# PicoUSBMotherboardV1_1.net
KiCad netlist of a schematic drawn in EasyEDA Pro
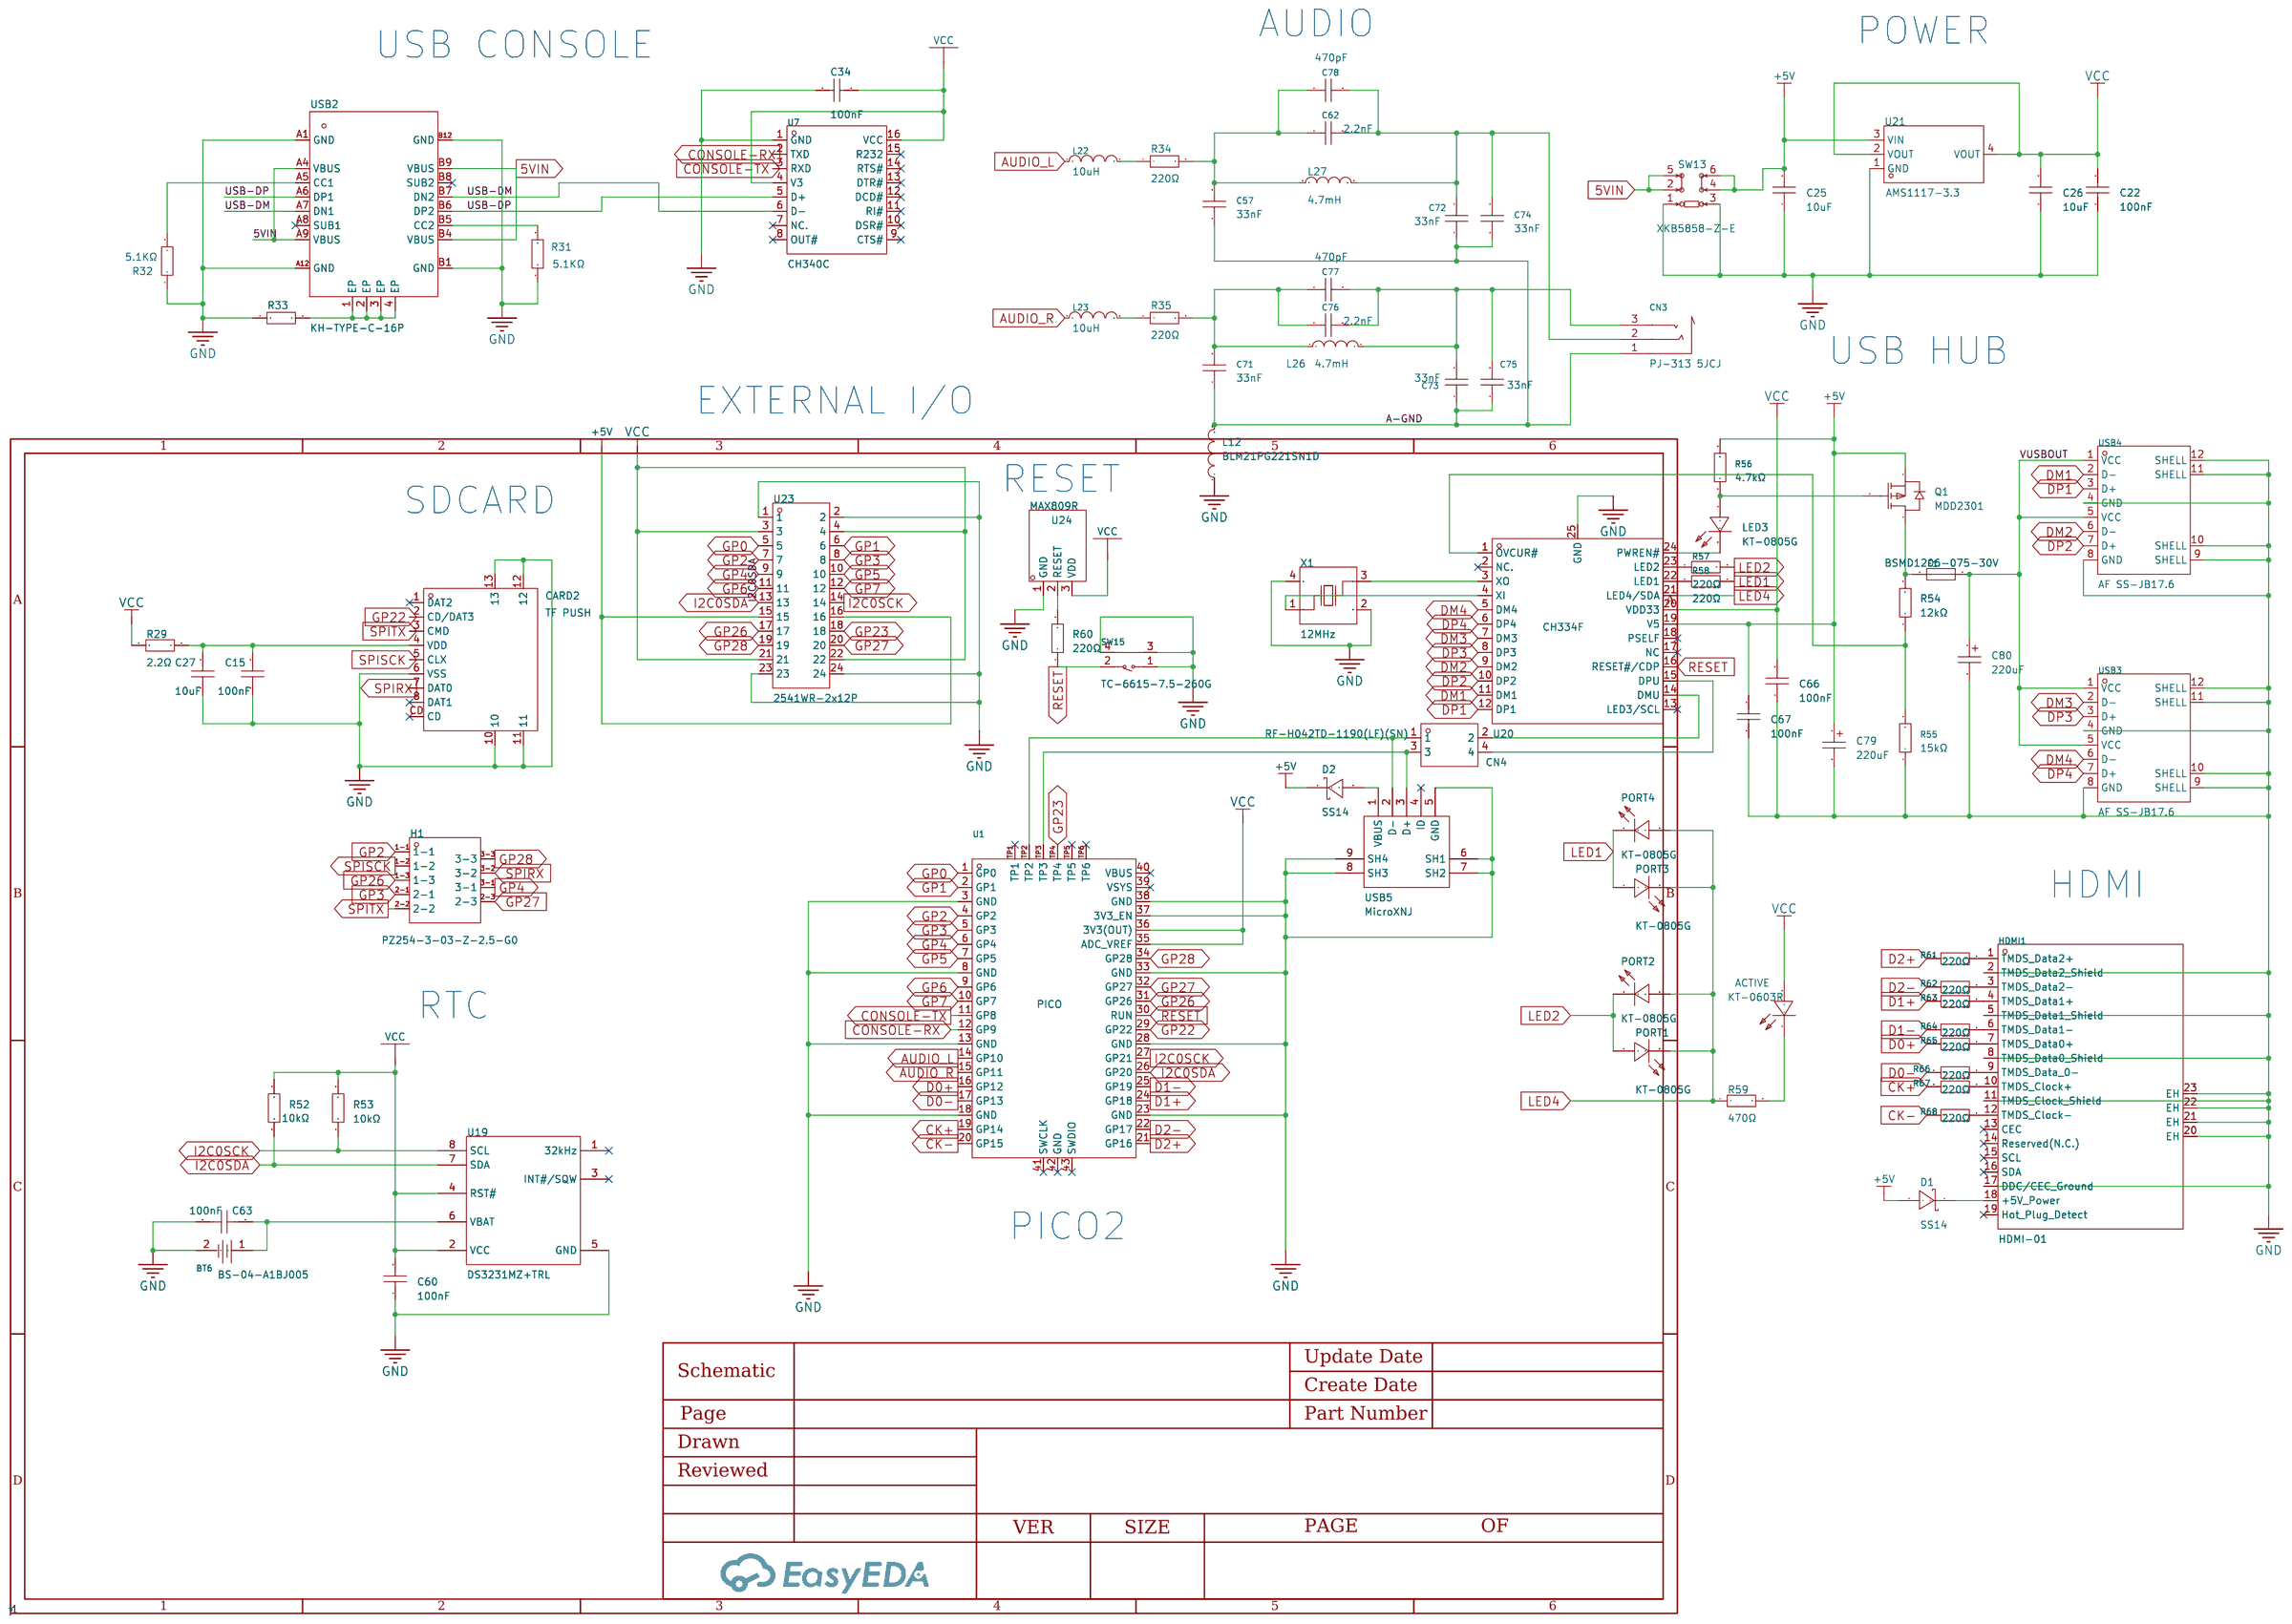
[diagram p0: schematic sheet]

(export (version "E")
  (design (tool "Eeschema 10.0.6"))
  (components
    (comp (ref "ACTIVE")
      (value "KT-0603R")
      (footprint "easyedapro:LED0603-RD")
      (fields (field (name "Manufacturer") "KENTO"))
      (libsource (lib "easyedapro") (part "KT-0603R"))
    )
    (comp (ref "BT6")
      (value "BS-04-A1BJ005")
      (footprint "easyedapro:BAT-TH_BS-04-A1BJ004")
      (fields (field (name "Manufacturer") "MYOUNG(美阳)"))
      (libsource (lib "easyedapro") (part "BS-04-A1BJ005"))
    )
    (comp (ref "C15")
      (value "100nF")
      (fields
        (field (name "Manufacturer Part") "CL05B104KO5NNNC")
        (field (name "Manufacturer") "SAMSUNG(三星)")
      )
      (libsource (lib "easyedapro") (part "cl10a225ko8nnnc"))
    )
    (comp (ref "C22")
      (value "100nF")
      (fields
        (field (name "Manufacturer Part") "CL05B104KO5NNNC")
        (field (name "Manufacturer") "SAMSUNG(三星)")
      )
      (libsource (lib "easyedapro") (part "cl10a225ko8nnnc"))
    )
    (comp (ref "C25")
      (value "10uF")
      (footprint "easyedapro:C1206")
      (fields
        (field (name "Manufacturer Part") "CL31A106KBHNNNE")
        (field (name "Manufacturer") "SAMSUNG(三星)")
      )
      (libsource (lib "easyedapro") (part "CL31A106KBHNNNE"))
    )
    (comp (ref "C26")
      (value "10uF")
      (footprint "easyedapro:C1206")
      (fields
        (field (name "Manufacturer Part") "CL31A106KBHNNNE")
        (field (name "Manufacturer") "SAMSUNG(三星)")
      )
      (libsource (lib "easyedapro") (part "CL31A106KBHNNNE"))
    )
    (comp (ref "C27")
      (value "10uF")
      (footprint "easyedapro:C1206")
      (fields
        (field (name "Manufacturer Part") "CL31A106KBHNNNE")
        (field (name "Manufacturer") "SAMSUNG(三星)")
      )
      (libsource (lib "easyedapro") (part "CL31A106KBHNNNE"))
    )
    (comp (ref "C34")
      (value "100nF")
      (fields
        (field (name "Manufacturer Part") "CL05B104KO5NNNC")
        (field (name "Manufacturer") "SAMSUNG(三星)")
      )
      (libsource (lib "easyedapro") (part "cl10a225ko8nnnc"))
    )
    (comp (ref "C57")
      (value "33nF")
      (footprint "easyedapro:C0805")
      (fields (field (name "Manufacturer Part") "0805B333K500NT") (field (name "Manufacturer") "FH(风华)"))
      (libsource (lib "easyedapro") (part "0805B333K500NT"))
    )
    (comp (ref "C60")
      (value "100nF")
      (fields
        (field (name "Manufacturer Part") "CL05B104KO5NNNC")
        (field (name "Manufacturer") "SAMSUNG(三星)")
      )
      (libsource (lib "easyedapro") (part "CL10A225KO8NNNC"))
    )
    (comp (ref "C62")
      (value "2.2nF")
      (footprint "easyedapro:C0805")
      (fields
        (field (name "Manufacturer Part") "CL21C222JBFNNNE")
        (field (name "Manufacturer") "SAMSUNG(三星)")
      )
      (libsource (lib "easyedapro") (part "CL21C222JBFNNNE"))
    )
    (comp (ref "C63")
      (value "100nF")
      (footprint "easyedapro:C0402")
      (fields
        (field (name "Manufacturer Part") "CL05B104KB54PNC")
        (field (name "Manufacturer") "SAMSUNG(三星)")
      )
      (libsource (lib "easyedapro") (part "CL05B104KB54PNC"))
    )
    (comp (ref "C66")
      (value "100nF")
      (fields
        (field (name "Manufacturer Part") "CL05B104KO5NNNC")
        (field (name "Manufacturer") "SAMSUNG(三星)")
      )
      (libsource (lib "easyedapro") (part "cl10a225ko8nnnc"))
    )
    (comp (ref "C67")
      (value "100nF")
      (fields
        (field (name "Manufacturer Part") "CL05B104KO5NNNC")
        (field (name "Manufacturer") "SAMSUNG(三星)")
      )
      (libsource (lib "easyedapro") (part "cl10a225ko8nnnc"))
    )
    (comp (ref "C71")
      (value "33nF")
      (footprint "easyedapro:C0805")
      (fields (field (name "Manufacturer Part") "0805B333K500NT") (field (name "Manufacturer") "FH(风华)"))
      (libsource (lib "easyedapro") (part "0805B333K500NT"))
    )
    (comp (ref "C72")
      (value "33nF")
      (footprint "easyedapro:C0805")
      (fields (field (name "Manufacturer Part") "0805B333K500NT") (field (name "Manufacturer") "FH(风华)"))
      (libsource (lib "easyedapro") (part "0805B333K500NT"))
    )
    (comp (ref "C73")
      (value "33nF")
      (footprint "easyedapro:C0805")
      (fields (field (name "Manufacturer Part") "0805B333K500NT") (field (name "Manufacturer") "FH(风华)"))
      (libsource (lib "easyedapro") (part "0805B333K500NT"))
    )
    (comp (ref "C74")
      (value "33nF")
      (footprint "easyedapro:C0805")
      (fields (field (name "Manufacturer Part") "0805B333K500NT") (field (name "Manufacturer") "FH(风华)"))
      (libsource (lib "easyedapro") (part "0805B333K500NT"))
    )
    (comp (ref "C75")
      (value "33nF")
      (footprint "easyedapro:C0805")
      (fields (field (name "Manufacturer Part") "0805B333K500NT") (field (name "Manufacturer") "FH(风华)"))
      (libsource (lib "easyedapro") (part "0805B333K500NT"))
    )
    (comp (ref "C76")
      (value "2.2nF")
      (footprint "easyedapro:C0805")
      (fields
        (field (name "Manufacturer Part") "CL21C222JBFNNNE")
        (field (name "Manufacturer") "SAMSUNG(三星)")
      )
      (libsource (lib "easyedapro") (part "CL21C222JBFNNNE"))
    )
    (comp (ref "C77")
      (value "470pF")
      (footprint "easyedapro:C0603")
      (fields (field (name "Manufacturer Part") "0603B471K500NT") (field (name "Manufacturer") "FH(风华)"))
      (libsource (lib "easyedapro") (part "0603B471K500NT"))
    )
    (comp (ref "C78")
      (value "470pF")
      (footprint "easyedapro:C0603")
      (fields (field (name "Manufacturer Part") "0603B471K500NT") (field (name "Manufacturer") "FH(风华)"))
      (libsource (lib "easyedapro") (part "0603B471K500NT"))
    )
    (comp (ref "C79")
      (value "220uF")
      (footprint "easyedapro:CASE-D_7343")
      (fields (field (name "Manufacturer Part") "TAJD227K010RNJ") (field (name "Manufacturer") "Kyocera AVX"))
      (libsource (lib "easyedapro") (part "TAJD227K010RNJ"))
    )
    (comp (ref "C80")
      (value "220uF")
      (footprint "easyedapro:CASE-D_7343")
      (fields (field (name "Manufacturer Part") "TAJD227K010RNJ") (field (name "Manufacturer") "Kyocera AVX"))
      (libsource (lib "easyedapro") (part "TAJD227K010RNJ"))
    )
    (comp (ref "CARD2")
      (value "TF PUSH")
      (footprint "easyedapro:TF-SMD_TF-PUSH")
      (fields (field (name "Manufacturer") "SHOU HAN(首韩)"))
      (libsource (lib "easyedapro") (part "TF PUSH"))
    )
    (comp (ref "CN3")
      (value "PJ-313 5JCJ")
      (footprint "easyedapro:AUDIO-TH_PJ-313_5JCJ")
      (fields (field (name "Manufacturer") "SHOU HAN(首韩)"))
      (libsource (lib "easyedapro") (part "PJ-313 5JCJ"))
    )
    (comp (ref "CN4")
      (value "RF-H042TD-1190(LF)(SN)")
      (footprint "easyedapro:HDR-TH_4P-P2.54-V-M-R2-C2-S2.54-1")
      (fields (field (name "Manufacturer") "JST"))
      (libsource (lib "easyedapro") (part "RF-H042TD-1190 (LF)(SN)"))
    )
    (comp (ref "D1")
      (value "SS14")
      (footprint "easyedapro:SMA_L4.2-W2.6-LS5.3-RD")
      (fields (field (name "Manufacturer") "MDD(辰达半导体)"))
      (libsource (lib "easyedapro") (part "SS14"))
    )
    (comp (ref "D2")
      (value "SS14")
      (footprint "easyedapro:SMA_L4.2-W2.6-LS5.3-RD")
      (fields (field (name "Manufacturer") "MDD(辰达半导体)"))
      (libsource (lib "easyedapro") (part "SS14"))
    )
    (comp (ref "F1")
      (value "BSMD1206-075-30V")
      (footprint "easyedapro:F1206")
      (fields (field (name "Manufacturer") "BHFUSE(佰宏)"))
      (libsource (lib "easyedapro") (part "BSMD1206-075-30V"))
    )
    (comp (ref "H1")
      (value "PZ254-3-03-Z-2.5-G0")
      (footprint "easyedapro:HDR-TH_9P-P2.54-V-M-R3-C3-S2.54")
      (fields (field (name "Manufacturer") "HCTL(华灿天禄)"))
      (libsource (lib "easyedapro") (part "PZ254-3-03-Z-2.5-G0"))
    )
    (comp (ref "HDMI1")
      (value "HDMI-01")
      (footprint "easyedapro:USB-SMD_HDMI-01")
      (fields (field (name "Manufacturer") "HCTL(华灿天禄)"))
      (libsource (lib "easyedapro") (part "HDMI-01"))
    )
    (comp (ref "L12")
      (value "BLM21PG221SN1D")
      (footprint "easyedapro:L0805")
      (fields (field (name "Manufacturer") "muRata(村田)"))
      (libsource (lib "easyedapro") (part "BLM21PG221SN1D"))
    )
    (comp (ref "L22")
      (value "10uH")
      (footprint "easyedapro:L0805")
      (fields
        (field (name "Manufacturer Part") "SDFL2012S100KTF")
        (field (name "Manufacturer") "Sunlord(顺络)")
      )
      (libsource (lib "easyedapro") (part "SDFL2012S100KTF"))
    )
    (comp (ref "L23")
      (value "10uH")
      (footprint "easyedapro:L0805")
      (fields
        (field (name "Manufacturer Part") "SDFL2012S100KTF")
        (field (name "Manufacturer") "Sunlord(顺络)")
      )
      (libsource (lib "easyedapro") (part "SDFL2012S100KTF"))
    )
    (comp (ref "L26")
      (value "4.7mH")
      (footprint "easyedapro:IND-SMD_L5.0-W5.0-1")
      (fields (field (name "Manufacturer Part") "YNR5040-472M") (field (name "Manufacturer") "YJYCOIN(益嘉源)"))
      (libsource (lib "easyedapro") (part "YNR5040-472M"))
    )
    (comp (ref "L27")
      (value "4.7mH")
      (footprint "easyedapro:IND-SMD_L5.0-W5.0-1")
      (fields (field (name "Manufacturer Part") "YNR5040-472M") (field (name "Manufacturer") "YJYCOIN(益嘉源)"))
      (libsource (lib "easyedapro") (part "YNR5040-472M"))
    )
    (comp (ref "LED3")
      (value "KT-0805G")
      (footprint "easyedapro:LED0805-R-RD")
      (fields (field (name "Manufacturer") "KENTO"))
      (libsource (lib "easyedapro") (part "0805G (Green)"))
    )
    (comp (ref "PORT1")
      (value "KT-0805G")
      (footprint "easyedapro:LED0805-R-RD")
      (fields (field (name "Manufacturer") "KENTO"))
      (libsource (lib "easyedapro") (part "0805G (Green)"))
    )
    (comp (ref "PORT2")
      (value "KT-0805G")
      (footprint "easyedapro:LED0805-R-RD")
      (fields (field (name "Manufacturer") "KENTO"))
      (libsource (lib "easyedapro") (part "0805G (Green)"))
    )
    (comp (ref "PORT3")
      (value "KT-0805G")
      (footprint "easyedapro:LED0805-R-RD")
      (fields (field (name "Manufacturer") "KENTO"))
      (libsource (lib "easyedapro") (part "0805G (Green)"))
    )
    (comp (ref "PORT4")
      (value "KT-0805G")
      (footprint "easyedapro:LED0805-R-RD")
      (fields (field (name "Manufacturer") "KENTO"))
      (libsource (lib "easyedapro") (part "0805G (Green)"))
    )
    (comp (ref "Q1")
      (value "MDD2301")
      (footprint "easyedapro:SOT-23-3_L2.9-W1.5-P1.90-LS2.6-BL")
      (fields (field (name "Manufacturer") "MDD(辰达半导体)"))
      (libsource (lib "easyedapro") (part "SI2301_C427391"))
    )
    (comp (ref "R29")
      (value "2.2Ω")
      (footprint "easyedapro:R0805")
      (fields (field (name "Manufacturer") "UNI-ROYAL(厚声)"))
      (libsource (lib "easyedapro") (part "0805W8F220KT5E"))
    )
    (comp (ref "R31")
      (value "5.1kΩ")
      (fields
        (field (name "Manufacturer Part") "5.1KΩ")
        (field (name "Manufacturer") "UNI-ROYAL(厚声)")
        (field (name "Tolerance") "±1%")
      )
      (libsource (lib "easyedapro") (part "0603waf5101t5e"))
    )
    (comp (ref "R32")
      (value "5.1kΩ")
      (fields
        (field (name "Manufacturer Part") "5.1KΩ")
        (field (name "Manufacturer") "UNI-ROYAL(厚声)")
        (field (name "Tolerance") "±1%")
      )
      (libsource (lib "easyedapro") (part "0603waf5101t5e"))
    )
    (comp (ref "R33")
      (value "1MΩ")
      (fields
        (field (name "Manufacturer Part") "0402WGF1004TCE")
        (field (name "Manufacturer") "UNI-ROYAL(厚声)")
      )
      (libsource (lib "easyedapro") (part "0603waf1004t5e"))
    )
    (comp (ref "R34")
      (value "220Ω")
      (footprint "easyedapro:R0603")
      (fields
        (field (name "Manufacturer Part") "0603WAF2200T5E")
        (field (name "Manufacturer") "UNI-ROYAL(厚声)")
      )
      (libsource (lib "easyedapro") (part "0603WAF2200T5E"))
    )
    (comp (ref "R35")
      (value "220Ω")
      (footprint "easyedapro:R0603")
      (fields
        (field (name "Manufacturer Part") "0603WAF2200T5E")
        (field (name "Manufacturer") "UNI-ROYAL(厚声)")
      )
      (libsource (lib "easyedapro") (part "0603WAF2200T5E"))
    )
    (comp (ref "R52")
      (value "10kΩ")
      (footprint "easyedapro:R0805")
      (fields
        (field (name "Manufacturer Part") "0805W8F1002T5E")
        (field (name "Manufacturer") "UNI-ROYAL(厚声)")
      )
      (libsource (lib "easyedapro") (part "0805W8F1002T5E"))
    )
    (comp (ref "R53")
      (value "10kΩ")
      (footprint "easyedapro:R0805")
      (fields
        (field (name "Manufacturer Part") "0805W8F1002T5E")
        (field (name "Manufacturer") "UNI-ROYAL(厚声)")
      )
      (libsource (lib "easyedapro") (part "0805W8F1002T5E"))
    )
    (comp (ref "R54")
      (value "12kΩ")
      (footprint "easyedapro:R0603")
      (fields
        (field (name "Manufacturer Part") "0603WAF1202T5E")
        (field (name "Manufacturer") "UNI-ROYAL(厚声)")
      )
      (libsource (lib "easyedapro") (part "0603WAF1202T5E"))
    )
    (comp (ref "R55")
      (value "15kΩ")
      (footprint "easyedapro:R0603")
      (fields
        (field (name "Manufacturer Part") "0603WAF1502T5E")
        (field (name "Manufacturer") "UNI-ROYAL(厚声)")
      )
      (libsource (lib "easyedapro") (part "0603WAF1502T5E"))
    )
    (comp (ref "R56")
      (value "4.7kΩ")
      (footprint "easyedapro:R0805")
      (fields
        (field (name "Manufacturer Part") "0805W8F4701T5E")
        (field (name "Manufacturer") "UNI-ROYAL(厚声)")
      )
      (libsource (lib "easyedapro") (part "0805W8F4701T5E"))
    )
    (comp (ref "R57")
      (value "220Ω")
      (footprint "easyedapro:R0805")
      (fields
        (field (name "Manufacturer Part") "0805W8F2200T5E")
        (field (name "Manufacturer") "UNI-ROYAL(厚声)")
      )
      (libsource (lib "easyedapro") (part "0805W8F2200T5E"))
    )
    (comp (ref "R58")
      (value "220Ω")
      (footprint "easyedapro:R0805")
      (fields
        (field (name "Manufacturer Part") "0805W8F2200T5E")
        (field (name "Manufacturer") "UNI-ROYAL(厚声)")
      )
      (libsource (lib "easyedapro") (part "0805W8F2200T5E"))
    )
    (comp (ref "R59")
      (value "470Ω")
      (footprint "easyedapro:R0603")
      (fields
        (field (name "Manufacturer Part") "0603WAF4700T5E")
        (field (name "Manufacturer") "UNI-ROYAL(厚声)")
      )
      (libsource (lib "easyedapro") (part "0603WAF4700T5E"))
    )
    (comp (ref "R60")
      (value "220Ω")
      (footprint "easyedapro:R0603")
      (fields
        (field (name "Manufacturer Part") "0603WAF2200T5E")
        (field (name "Manufacturer") "UNI-ROYAL(厚声)")
      )
      (libsource (lib "easyedapro") (part "0603WAF2200T5E"))
    )
    (comp (ref "R61")
      (value "220Ω")
      (footprint "easyedapro:R0603")
      (fields
        (field (name "Manufacturer Part") "0603WAF2200T5E")
        (field (name "Manufacturer") "UNI-ROYAL(厚声)")
      )
      (libsource (lib "easyedapro") (part "0603WAF2200T5E"))
    )
    (comp (ref "R62")
      (value "220Ω")
      (footprint "easyedapro:R0603")
      (fields
        (field (name "Manufacturer Part") "0603WAF2200T5E")
        (field (name "Manufacturer") "UNI-ROYAL(厚声)")
      )
      (libsource (lib "easyedapro") (part "0603WAF2200T5E"))
    )
    (comp (ref "R63")
      (value "220Ω")
      (footprint "easyedapro:R0603")
      (fields
        (field (name "Manufacturer Part") "0603WAF2200T5E")
        (field (name "Manufacturer") "UNI-ROYAL(厚声)")
      )
      (libsource (lib "easyedapro") (part "0603WAF2200T5E"))
    )
    (comp (ref "R64")
      (value "220Ω")
      (footprint "easyedapro:R0603")
      (fields
        (field (name "Manufacturer Part") "0603WAF2200T5E")
        (field (name "Manufacturer") "UNI-ROYAL(厚声)")
      )
      (libsource (lib "easyedapro") (part "0603WAF2200T5E"))
    )
    (comp (ref "R65")
      (value "220Ω")
      (footprint "easyedapro:R0603")
      (fields
        (field (name "Manufacturer Part") "0603WAF2200T5E")
        (field (name "Manufacturer") "UNI-ROYAL(厚声)")
      )
      (libsource (lib "easyedapro") (part "0603WAF2200T5E"))
    )
    (comp (ref "R66")
      (value "220Ω")
      (footprint "easyedapro:R0603")
      (fields
        (field (name "Manufacturer Part") "0603WAF2200T5E")
        (field (name "Manufacturer") "UNI-ROYAL(厚声)")
      )
      (libsource (lib "easyedapro") (part "0603WAF2200T5E"))
    )
    (comp (ref "R67")
      (value "220Ω")
      (footprint "easyedapro:R0603")
      (fields
        (field (name "Manufacturer Part") "0603WAF2200T5E")
        (field (name "Manufacturer") "UNI-ROYAL(厚声)")
      )
      (libsource (lib "easyedapro") (part "0603WAF2200T5E"))
    )
    (comp (ref "R68")
      (value "220Ω")
      (footprint "easyedapro:R0603")
      (fields
        (field (name "Manufacturer Part") "0603WAF2200T5E")
        (field (name "Manufacturer") "UNI-ROYAL(厚声)")
      )
      (libsource (lib "easyedapro") (part "0603WAF2200T5E"))
    )
    (comp (ref "SW13")
      (value "XKB5858-Z-E")
      (footprint "easyedapro:SW-TH_XKB5858-Z-E")
      (fields (field (name "Manufacturer") "XKB Connectivity(中国星坤)"))
      (libsource (lib "easyedapro") (part "XKB5858-Z-E"))
    )
    (comp (ref "SW15")
      (value "TC-6615-7.5-260G")
      (footprint "easyedapro:SW-TH_4P-L7.5-W7.5-P4.50")
      (fields (field (name "Manufacturer") "HCTL(华灿天禄)"))
      (libsource (lib "easyedapro") (part "TC-6615-7.5-260G"))
    )
    (comp (ref "U1")
      (value "PICO")
      (footprint "easyedapro:COMM-SMD_L51.0-W21.0-P2.54_SC0916")
      (fields (field (name "Manufacturer") "Raspberry Pi(树莓派)"))
      (libsource (lib "easyedapro") (part "PICO"))
    )
    (comp (ref "U7")
      (value "CH340C")
      (footprint "easyedapro:SOP-16_L10.0-W3.9-P1.27-LS6.0-BL")
      (fields (field (name "Manufacturer") "WCH(南京沁恒)"))
      (libsource (lib "easyedapro") (part "CH340C"))
    )
    (comp (ref "U19")
      (value "DS3231MZ+TRL")
      (footprint "easyedapro:SOIC-8_L4.9-W3.9-P1.27-LS6.0-BL")
      (fields (field (name "Manufacturer") "ADI(亚德诺)/MAXIM(美信)"))
      (libsource (lib "easyedapro") (part "DS3231MZ+"))
    )
    (comp (ref "U20")
      (value "CH334F")
      (footprint "easyedapro:QFN-24_L4.0-W4.0-P0.50-BL-EP2.8")
      (fields (field (name "Manufacturer") "WCH(南京沁恒)"))
      (libsource (lib "easyedapro") (part "CH334F_C5187527"))
    )
    (comp (ref "U21")
      (value "AMS1117-3.3")
      (footprint "easyedapro:SOT-223-3_L6.5-W3.4-P2.30-LS7.0-BR")
      (fields (field (name "Manufacturer") "AMS"))
      (libsource (lib "easyedapro") (part "AMS1117-3.3"))
    )
    (comp (ref "U23")
      (value "2541WR-2x12P")
      (footprint "easyedapro:HDR-TH_24P-P2.54-H-M-R2-C12-S2.54-N")
      (fields (field (name "Manufacturer") "HanElectricity(瀚源)"))
      (libsource (lib "easyedapro") (part "2541WR-2X12P"))
    )
    (comp (ref "U24")
      (value "MAX809R")
      (footprint "easyedapro:SOT-23-3_L2.9-W1.3-P1.90-LS2.4-BR")
      (fields (field (name "Manufacturer") "UMW(友台半导体)"))
      (libsource (lib "easyedapro") (part "MAX809R"))
    )
    (comp (ref "USB2")
      (value "KH-TYPE-C-16P")
      (footprint "easyedapro:USB-C-SMD_KH-TYPE-C-16P")
      (fields (field (name "Manufacturer") "kinghelm(金航标)"))
      (libsource (lib "easyedapro") (part "KH-TYPE-C-16P"))
    )
    (comp (ref "USB3")
      (value "AF SS-JB17.6")
      (footprint "easyedapro:USB-A-TH_AF-SS-JB17.6")
      (fields (field (name "Manufacturer") "SHOU HAN(首韩)"))
      (libsource (lib "easyedapro") (part "AF SS-JB17.6"))
    )
    (comp (ref "USB4")
      (value "AF SS-JB17.6")
      (footprint "easyedapro:USB-A-TH_AF-SS-JB17.6")
      (fields (field (name "Manufacturer") "SHOU HAN(首韩)"))
      (libsource (lib "easyedapro") (part "AF SS-JB17.6"))
    )
    (comp (ref "USB5")
      (value "MicroXNJ")
      (footprint "easyedapro:MICRO-USB-SMD_MICROXNJ")
      (fields (field (name "Manufacturer") "SHOU HAN(首韩)"))
      (libsource (lib "easyedapro") (part "MICROXNJ"))
    )
    (comp (ref "X1")
      (value "12MHz")
      (footprint "easyedapro:OSC-SMD_4P-L3.2-W2.5-BL")
      (fields (field (name "Manufacturer Part") "X322512MSB4SI") (field (name "Manufacturer") "YXC(扬兴晶振)"))
      (libsource (lib "easyedapro") (part "X322512MSB4SI"))
    )
  )
  (nets
    (net (code "1") (name "+5V") (class "Default")
      (node (ref "C25") (pin "2") (pinfunction "2_2") (pintype "input"))
      (node (ref "C67") (pin "2") (pinfunction "2_2") (pintype "input"))
      (node (ref "C79") (pin "1") (pinfunction "1_1") (pintype "input"))
      (node (ref "D1") (pin "2") (pinfunction "A_2") (pintype "unspecified"))
      (node (ref "D2") (pin "1") (pinfunction "K_1") (pintype "unspecified"))
      (node (ref "Q1") (pin "2") (pinfunction "S_2") (pintype "unspecified"))
      (node (ref "R56") (pin "2") (pinfunction "2_2") (pintype "input"))
      (node (ref "SW13") (pin "4") (pinfunction "4_4") (pintype "input"))
      (node (ref "SW13") (pin "6") (pinfunction "6_6") (pintype "input"))
      (node (ref "U20") (pin "19") (pinfunction "V5_19") (pintype "unspecified"))
      (node (ref "U21") (pin "3") (pinfunction "VIN_3") (pintype "input"))
      (node (ref "U23") (pin "15") (pinfunction "15_15") (pintype "unspecified"))
      (node (ref "U23") (pin "16") (pinfunction "16_16") (pintype "unspecified"))
    )
    (net (code "2") (name "/A-GND") (class "Default")
      (node (ref "C57") (pin "1") (pinfunction "1_1") (pintype "input"))
      (node (ref "C71") (pin "1") (pinfunction "1_1") (pintype "input"))
      (node (ref "C72") (pin "1") (pinfunction "1_1") (pintype "input"))
      (node (ref "C73") (pin "1") (pinfunction "1_1") (pintype "input"))
      (node (ref "C74") (pin "1") (pinfunction "1_1") (pintype "input"))
      (node (ref "C75") (pin "1") (pinfunction "1_1") (pintype "input"))
      (node (ref "CN3") (pin "1") (pinfunction "1_1") (pintype "input"))
      (node (ref "L12") (pin "2") (pinfunction "2_2") (pintype "input"))
    )
    (net (code "3") (name "/USB-DM") (class "Default")
      (node (ref "U7") (pin "6") (pinfunction "D-_6") (pintype "input"))
      (node (ref "USB2") (pin "A7") (pinfunction "DN1_A7") (pintype "input"))
      (node (ref "USB2") (pin "B7") (pinfunction "DN2_B7") (pintype "input"))
    )
    (net (code "4") (name "/USB-DP") (class "Default")
      (node (ref "U7") (pin "5") (pinfunction "D+_5") (pintype "input"))
      (node (ref "USB2") (pin "A6") (pinfunction "DP1_A6") (pintype "input"))
      (node (ref "USB2") (pin "B6") (pinfunction "DP2_B6") (pintype "input"))
    )
    (net (code "5") (name "/VUSBOUT") (class "Default")
      (node (ref "C80") (pin "1") (pinfunction "1_1") (pintype "input"))
      (node (ref "F1") (pin "2") (pinfunction "2_2") (pintype "input"))
      (node (ref "USB3") (pin "1") (pinfunction "VCC_1") (pintype "input"))
      (node (ref "USB3") (pin "5") (pinfunction "VCC_5") (pintype "input"))
      (node (ref "USB4") (pin "1") (pinfunction "VCC_1") (pintype "input"))
      (node (ref "USB4") (pin "5") (pinfunction "VCC_5") (pintype "input"))
    )
    (net (code "6") (name "5VIN") (class "Default")
      (node (ref "SW13") (pin "2") (pinfunction "2_2") (pintype "input"))
      (node (ref "SW13") (pin "5") (pinfunction "5_5") (pintype "input"))
      (node (ref "USB2") (pin "A4") (pinfunction "VBUS_A4") (pintype "input"))
      (node (ref "USB2") (pin "A9") (pinfunction "VBUS_A9") (pintype "input"))
      (node (ref "USB2") (pin "B4") (pinfunction "VBUS_B4") (pintype "input"))
      (node (ref "USB2") (pin "B9") (pinfunction "VBUS_B9") (pintype "input"))
    )
    (net (code "7") (name "AUDIO_L") (class "Default")
      (node (ref "L22") (pin "1") (pinfunction "1_1") (pintype "input"))
      (node (ref "U1") (pin "14") (pinfunction "GP10_14") (pintype "input"))
    )
    (net (code "8") (name "AUDIO_R") (class "Default")
      (node (ref "L23") (pin "1") (pinfunction "1_1") (pintype "input"))
      (node (ref "U1") (pin "15") (pinfunction "GP11_15") (pintype "input"))
    )
    (net (code "9") (name "CK+") (class "Default")
      (node (ref "R67") (pin "1") (pinfunction "1_1") (pintype "input"))
      (node (ref "U1") (pin "19") (pinfunction "GP14_19") (pintype "input"))
    )
    (net (code "10") (name "CK-") (class "Default")
      (node (ref "R68") (pin "1") (pinfunction "1_1") (pintype "input"))
      (node (ref "U1") (pin "20") (pinfunction "GP15_20") (pintype "input"))
    )
    (net (code "11") (name "CONSOLE-RX") (class "Default")
      (node (ref "U1") (pin "12") (pinfunction "GP9_12") (pintype "input"))
      (node (ref "U7") (pin "2") (pinfunction "TXD_2") (pintype "input"))
    )
    (net (code "12") (name "CONSOLE-TX") (class "Default")
      (node (ref "U1") (pin "11") (pinfunction "GP8_11") (pintype "input"))
      (node (ref "U7") (pin "3") (pinfunction "RXD_3") (pintype "input"))
    )
    (net (code "13") (name "D0+") (class "Default")
      (node (ref "R65") (pin "1") (pinfunction "1_1") (pintype "input"))
      (node (ref "U1") (pin "16") (pinfunction "GP12_16") (pintype "input"))
    )
    (net (code "14") (name "D0-") (class "Default")
      (node (ref "R66") (pin "1") (pinfunction "1_1") (pintype "input"))
      (node (ref "U1") (pin "17") (pinfunction "GP13_17") (pintype "input"))
    )
    (net (code "15") (name "D1+") (class "Default")
      (node (ref "R63") (pin "1") (pinfunction "1_1") (pintype "input"))
      (node (ref "U1") (pin "24") (pinfunction "GP18_24") (pintype "input"))
    )
    (net (code "16") (name "D1-") (class "Default")
      (node (ref "R64") (pin "1") (pinfunction "1_1") (pintype "input"))
      (node (ref "U1") (pin "25") (pinfunction "GP19_25") (pintype "input"))
    )
    (net (code "17") (name "D2+") (class "Default")
      (node (ref "R61") (pin "1") (pinfunction "1_1") (pintype "input"))
      (node (ref "U1") (pin "21") (pinfunction "GP16_21") (pintype "input"))
    )
    (net (code "18") (name "D2-") (class "Default")
      (node (ref "R62") (pin "1") (pinfunction "1_1") (pintype "input"))
      (node (ref "U1") (pin "22") (pinfunction "GP17_22") (pintype "input"))
    )
    (net (code "19") (name "DM1") (class "Default")
      (node (ref "U20") (pin "11") (pinfunction "DM1_11") (pintype "unspecified"))
      (node (ref "USB4") (pin "2") (pinfunction "D-_2") (pintype "input"))
    )
    (net (code "20") (name "DM2") (class "Default")
      (node (ref "U20") (pin "9") (pinfunction "DM2_9") (pintype "unspecified"))
      (node (ref "USB4") (pin "6") (pinfunction "D-_6") (pintype "input"))
    )
    (net (code "21") (name "DM3") (class "Default")
      (node (ref "U20") (pin "7") (pinfunction "DM3_7") (pintype "unspecified"))
      (node (ref "USB3") (pin "2") (pinfunction "D-_2") (pintype "input"))
    )
    (net (code "22") (name "DM4") (class "Default")
      (node (ref "U20") (pin "5") (pinfunction "DM4_5") (pintype "unspecified"))
      (node (ref "USB3") (pin "6") (pinfunction "D-_6") (pintype "input"))
    )
    (net (code "23") (name "DP1") (class "Default")
      (node (ref "U20") (pin "12") (pinfunction "DP1_12") (pintype "unspecified"))
      (node (ref "USB4") (pin "3") (pinfunction "D+_3") (pintype "input"))
    )
    (net (code "24") (name "DP2") (class "Default")
      (node (ref "U20") (pin "10") (pinfunction "DP2_10") (pintype "unspecified"))
      (node (ref "USB4") (pin "7") (pinfunction "D+_7") (pintype "input"))
    )
    (net (code "25") (name "DP3") (class "Default")
      (node (ref "U20") (pin "8") (pinfunction "DP3_8") (pintype "unspecified"))
      (node (ref "USB3") (pin "3") (pinfunction "D+_3") (pintype "input"))
    )
    (net (code "26") (name "DP4") (class "Default")
      (node (ref "U20") (pin "6") (pinfunction "DP4_6") (pintype "unspecified"))
      (node (ref "USB3") (pin "7") (pinfunction "D+_7") (pintype "input"))
    )
    (net (code "27") (name "GND") (class "Default")
      (node (ref "BT6") (pin "2") (pinfunction "2_2") (pintype "input"))
      (node (ref "C15") (pin "1") (pinfunction "1_1") (pintype "input"))
      (node (ref "C22") (pin "1") (pinfunction "1_1") (pintype "input"))
      (node (ref "C25") (pin "1") (pinfunction "1_1") (pintype "input"))
      (node (ref "C26") (pin "1") (pinfunction "1_1") (pintype "input"))
      (node (ref "C27") (pin "1") (pinfunction "1_1") (pintype "input"))
      (node (ref "C34") (pin "2") (pinfunction "2_2") (pintype "input"))
      (node (ref "C60") (pin "1") (pinfunction "1_1") (pintype "input"))
      (node (ref "C63") (pin "2") (pinfunction "2_2") (pintype "input"))
      (node (ref "C66") (pin "1") (pinfunction "1_1") (pintype "input"))
      (node (ref "C67") (pin "1") (pinfunction "1_1") (pintype "input"))
      (node (ref "C79") (pin "2") (pinfunction "2_2") (pintype "input"))
      (node (ref "C80") (pin "2") (pinfunction "2_2") (pintype "input"))
      (node (ref "CARD2") (pin "10") (pinfunction "10_10") (pintype "input"))
      (node (ref "CARD2") (pin "11") (pinfunction "11_11") (pintype "input"))
      (node (ref "CARD2") (pin "12") (pinfunction "12_12") (pintype "input"))
      (node (ref "CARD2") (pin "13") (pinfunction "13_13") (pintype "input"))
      (node (ref "CARD2") (pin "6") (pinfunction "VSS_6") (pintype "input"))
      (node (ref "HDMI1") (pin "11") (pinfunction "TMDS_Clock_Shield_11") (pintype "input"))
      (node (ref "HDMI1") (pin "17") (pinfunction "DDC/CEC_Ground_17") (pintype "input"))
      (node (ref "HDMI1") (pin "2") (pinfunction "TMDS_Data2_Shield_2") (pintype "input"))
      (node (ref "HDMI1") (pin "20") (pinfunction "EH_20") (pintype "input"))
      (node (ref "HDMI1") (pin "21") (pinfunction "EH_21") (pintype "input"))
      (node (ref "HDMI1") (pin "22") (pinfunction "EH_22") (pintype "input"))
      (node (ref "HDMI1") (pin "23") (pinfunction "EH_23") (pintype "input"))
      (node (ref "HDMI1") (pin "5") (pinfunction "TMDS_Data1_Shield_5") (pintype "input"))
      (node (ref "HDMI1") (pin "8") (pinfunction "TMDS_Data0_Shield_8") (pintype "input"))
      (node (ref "L12") (pin "1") (pinfunction "1_1") (pintype "input"))
      (node (ref "R31") (pin "1") (pinfunction "1_1") (pintype "input"))
      (node (ref "R32") (pin "1") (pinfunction "1_1") (pintype "input"))
      (node (ref "R33") (pin "1") (pinfunction "1_1") (pintype "input"))
      (node (ref "R55") (pin "1") (pinfunction "1_1") (pintype "input"))
      (node (ref "SW13") (pin "1") (pinfunction "1_1") (pintype "input"))
      (node (ref "SW13") (pin "3") (pinfunction "3_3") (pintype "input"))
      (node (ref "SW15") (pin "1") (pinfunction "1_1") (pintype "input"))
      (node (ref "SW15") (pin "3") (pinfunction "3_3") (pintype "input"))
      (node (ref "SW15") (pin "4") (pinfunction "4_4") (pintype "input"))
      (node (ref "U1") (pin "13") (pinfunction "GND_13") (pintype "input"))
      (node (ref "U1") (pin "18") (pinfunction "GND_18") (pintype "input"))
      (node (ref "U1") (pin "23") (pinfunction "GND_23") (pintype "input"))
      (node (ref "U1") (pin "28") (pinfunction "GND_28") (pintype "input"))
      (node (ref "U1") (pin "3") (pinfunction "GND_3") (pintype "input"))
      (node (ref "U1") (pin "33") (pinfunction "GND_33") (pintype "input"))
      (node (ref "U1") (pin "37") (pinfunction "3V3_EN_37") (pintype "input"))
      (node (ref "U1") (pin "38") (pinfunction "GND_38") (pintype "input"))
      (node (ref "U1") (pin "8") (pinfunction "GND_8") (pintype "input"))
      (node (ref "U19") (pin "5") (pinfunction "GND_5") (pintype "unspecified"))
      (node (ref "U20") (pin "25") (pinfunction "GND_25") (pintype "unspecified"))
      (node (ref "U21") (pin "1") (pinfunction "GND_1") (pintype "input"))
      (node (ref "U23") (pin "1") (pinfunction "1_1") (pintype "unspecified"))
      (node (ref "U23") (pin "2") (pinfunction "2_2") (pintype "unspecified"))
      (node (ref "U23") (pin "23") (pinfunction "23_23") (pintype "unspecified"))
      (node (ref "U23") (pin "24") (pinfunction "24_24") (pintype "unspecified"))
      (node (ref "U24") (pin "1") (pinfunction "GND_1") (pintype "unspecified"))
      (node (ref "U7") (pin "1") (pinfunction "GND_1") (pintype "input"))
      (node (ref "USB2") (pin "A1") (pinfunction "GND_A1") (pintype "input"))
      (node (ref "USB2") (pin "A12") (pinfunction "GND_A12") (pintype "input"))
      (node (ref "USB2") (pin "B1") (pinfunction "GND_B1") (pintype "input"))
      (node (ref "USB2") (pin "B12") (pinfunction "GND_B12") (pintype "input"))
      (node (ref "USB3") (pin "10") (pinfunction "SHELL_10") (pintype "input"))
      (node (ref "USB3") (pin "11") (pinfunction "SHELL_11") (pintype "input"))
      (node (ref "USB3") (pin "12") (pinfunction "SHELL_12") (pintype "input"))
      (node (ref "USB3") (pin "4") (pinfunction "GND_4") (pintype "input"))
      (node (ref "USB3") (pin "8") (pinfunction "GND_8") (pintype "input"))
      (node (ref "USB3") (pin "9") (pinfunction "SHELL_9") (pintype "input"))
      (node (ref "USB4") (pin "10") (pinfunction "SHELL_10") (pintype "input"))
      (node (ref "USB4") (pin "11") (pinfunction "SHELL_11") (pintype "input"))
      (node (ref "USB4") (pin "12") (pinfunction "SHELL_12") (pintype "input"))
      (node (ref "USB4") (pin "4") (pinfunction "GND_4") (pintype "input"))
      (node (ref "USB4") (pin "8") (pinfunction "GND_8") (pintype "input"))
      (node (ref "USB4") (pin "9") (pinfunction "SHELL_9") (pintype "input"))
      (node (ref "USB5") (pin "5") (pinfunction "GND_5") (pintype "unspecified"))
      (node (ref "USB5") (pin "6") (pinfunction "SH1_6") (pintype "unspecified"))
      (node (ref "USB5") (pin "7") (pinfunction "SH2_7") (pintype "unspecified"))
      (node (ref "USB5") (pin "8") (pinfunction "SH3_8") (pintype "unspecified"))
      (node (ref "USB5") (pin "9") (pinfunction "SH4_9") (pintype "unspecified"))
      (node (ref "X1") (pin "2") (pinfunction "GND_2") (pintype "unspecified"))
      (node (ref "X1") (pin "4") (pinfunction "GND_4") (pintype "unspecified"))
    )
    (net (code "28") (name "GP0") (class "Default")
      (node (ref "U1") (pin "1") (pinfunction "GP0_1") (pintype "input"))
      (node (ref "U23") (pin "5") (pinfunction "5_5") (pintype "unspecified"))
    )
    (net (code "29") (name "GP1") (class "Default")
      (node (ref "U1") (pin "2") (pinfunction "GP1_2") (pintype "input"))
      (node (ref "U23") (pin "6") (pinfunction "6_6") (pintype "unspecified"))
    )
    (net (code "30") (name "GP2") (class "Default")
      (node (ref "H1") (pin "1-1") (pinfunction "1-1_1-1") (pintype "unspecified"))
      (node (ref "U1") (pin "4") (pinfunction "GP2_4") (pintype "input"))
      (node (ref "U23") (pin "7") (pinfunction "7_7") (pintype "unspecified"))
    )
    (net (code "31") (name "GP3") (class "Default")
      (node (ref "H1") (pin "2-1") (pinfunction "2-1_2-1") (pintype "unspecified"))
      (node (ref "U1") (pin "5") (pinfunction "GP3_5") (pintype "input"))
      (node (ref "U23") (pin "8") (pinfunction "8_8") (pintype "unspecified"))
    )
    (net (code "32") (name "GP4") (class "Default")
      (node (ref "H1") (pin "3-1") (pinfunction "3-1_3-1") (pintype "unspecified"))
      (node (ref "U1") (pin "6") (pinfunction "GP4_6") (pintype "input"))
      (node (ref "U23") (pin "9") (pinfunction "9_9") (pintype "unspecified"))
    )
    (net (code "33") (name "GP5") (class "Default")
      (node (ref "U1") (pin "7") (pinfunction "GP5_7") (pintype "input"))
      (node (ref "U23") (pin "10") (pinfunction "10_10") (pintype "unspecified"))
    )
    (net (code "34") (name "GP6") (class "Default")
      (node (ref "U1") (pin "9") (pinfunction "GP6_9") (pintype "input"))
      (node (ref "U23") (pin "11") (pinfunction "11_11") (pintype "unspecified"))
    )
    (net (code "35") (name "GP7") (class "Default")
      (node (ref "U1") (pin "10") (pinfunction "GP7_10") (pintype "input"))
      (node (ref "U23") (pin "12") (pinfunction "12_12") (pintype "unspecified"))
    )
    (net (code "36") (name "GP22") (class "Default")
      (node (ref "CARD2") (pin "2") (pinfunction "CD/DAT3_2") (pintype "input"))
      (node (ref "U1") (pin "29") (pinfunction "GP22_29") (pintype "input"))
    )
    (net (code "37") (name "GP23") (class "Default")
      (node (ref "U1") (pin "TP4") (pinfunction "TP4_TP4") (pintype "input"))
      (node (ref "U23") (pin "18") (pinfunction "18_18") (pintype "unspecified"))
    )
    (net (code "38") (name "GP26") (class "Default")
      (node (ref "H1") (pin "1-3") (pinfunction "1-3_1-3") (pintype "unspecified"))
      (node (ref "U1") (pin "31") (pinfunction "GP26_31") (pintype "input"))
      (node (ref "U23") (pin "17") (pinfunction "17_17") (pintype "unspecified"))
    )
    (net (code "39") (name "GP27") (class "Default")
      (node (ref "H1") (pin "2-3") (pinfunction "2-3_2-3") (pintype "unspecified"))
      (node (ref "U1") (pin "32") (pinfunction "GP27_32") (pintype "input"))
      (node (ref "U23") (pin "20") (pinfunction "20_20") (pintype "unspecified"))
    )
    (net (code "40") (name "GP28") (class "Default")
      (node (ref "H1") (pin "3-3") (pinfunction "3-3_3-3") (pintype "unspecified"))
      (node (ref "U1") (pin "34") (pinfunction "GP28_34") (pintype "input"))
      (node (ref "U23") (pin "19") (pinfunction "19_19") (pintype "unspecified"))
    )
    (net (code "41") (name "I2C0SCK") (class "Default")
      (node (ref "R53") (pin "1") (pinfunction "1_1") (pintype "input"))
      (node (ref "U1") (pin "27") (pinfunction "GP21_27") (pintype "input"))
      (node (ref "U19") (pin "8") (pinfunction "SCL_8") (pintype "unspecified"))
      (node (ref "U23") (pin "14") (pinfunction "14_14") (pintype "unspecified"))
    )
    (net (code "42") (name "I2C0SDA") (class "Default")
      (node (ref "R52") (pin "1") (pinfunction "1_1") (pintype "input"))
      (node (ref "U1") (pin "26") (pinfunction "GP20_26") (pintype "input"))
      (node (ref "U19") (pin "7") (pinfunction "SDA_7") (pintype "bidirectional"))
      (node (ref "U23") (pin "13") (pinfunction "13_13") (pintype "unspecified"))
    )
    (net (code "43") (name "LED1") (class "Default")
      (node (ref "PORT3") (pin "1") (pinfunction "A_1") (pintype "unspecified"))
      (node (ref "PORT4") (pin "2") (pinfunction "K_2") (pintype "unspecified"))
      (node (ref "R58") (pin "2") (pinfunction "2_2") (pintype "input"))
    )
    (net (code "44") (name "LED2") (class "Default")
      (node (ref "PORT1") (pin "1") (pinfunction "A_1") (pintype "unspecified"))
      (node (ref "PORT2") (pin "2") (pinfunction "K_2") (pintype "unspecified"))
      (node (ref "R57") (pin "2") (pinfunction "2_2") (pintype "input"))
    )
    (net (code "45") (name "LED4") (class "Default")
      (node (ref "PORT1") (pin "2") (pinfunction "K_2") (pintype "unspecified"))
      (node (ref "PORT2") (pin "1") (pinfunction "A_1") (pintype "unspecified"))
      (node (ref "PORT3") (pin "2") (pinfunction "K_2") (pintype "unspecified"))
      (node (ref "PORT4") (pin "1") (pinfunction "A_1") (pintype "unspecified"))
      (node (ref "R59") (pin "1") (pinfunction "1_1") (pintype "input"))
      (node (ref "U20") (pin "21") (pinfunction "LED4/SDA_21") (pintype "unspecified"))
    )
    (net (code "46") (name "Net-(ACTIVE-K)") (class "Default")
      (node (ref "ACTIVE") (pin "1") (pinfunction "K_1") (pintype "input"))
      (node (ref "R59") (pin "2") (pinfunction "2_2") (pintype "input"))
    )
    (net (code "47") (name "Net-(C57-Pad2)") (class "Default")
      (node (ref "C57") (pin "2") (pinfunction "2_2") (pintype "input"))
      (node (ref "C62") (pin "1") (pinfunction "1_1") (pintype "input"))
      (node (ref "C78") (pin "1") (pinfunction "1_1") (pintype "input"))
      (node (ref "L27") (pin "1") (pinfunction "1_1") (pintype "unspecified"))
      (node (ref "R34") (pin "2") (pinfunction "2_2") (pintype "input"))
    )
    (net (code "48") (name "Net-(C62-Pad2)") (class "Default")
      (node (ref "C62") (pin "2") (pinfunction "2_2") (pintype "input"))
      (node (ref "C72") (pin "2") (pinfunction "2_2") (pintype "input"))
      (node (ref "C74") (pin "2") (pinfunction "2_2") (pintype "input"))
      (node (ref "C78") (pin "2") (pinfunction "2_2") (pintype "input"))
      (node (ref "CN3") (pin "2") (pinfunction "2_2") (pintype "input"))
      (node (ref "L27") (pin "2") (pinfunction "2_2") (pintype "unspecified"))
    )
    (net (code "49") (name "Net-(C71-Pad2)") (class "Default")
      (node (ref "C71") (pin "2") (pinfunction "2_2") (pintype "input"))
      (node (ref "C76") (pin "1") (pinfunction "1_1") (pintype "input"))
      (node (ref "C77") (pin "1") (pinfunction "1_1") (pintype "input"))
      (node (ref "L26") (pin "1") (pinfunction "1_1") (pintype "unspecified"))
      (node (ref "R35") (pin "2") (pinfunction "2_2") (pintype "input"))
    )
    (net (code "50") (name "Net-(C73-Pad2)") (class "Default")
      (node (ref "C73") (pin "2") (pinfunction "2_2") (pintype "input"))
      (node (ref "C75") (pin "2") (pinfunction "2_2") (pintype "input"))
      (node (ref "C76") (pin "2") (pinfunction "2_2") (pintype "input"))
      (node (ref "C77") (pin "2") (pinfunction "2_2") (pintype "input"))
      (node (ref "CN3") (pin "3") (pinfunction "3_3") (pintype "input"))
      (node (ref "L26") (pin "2") (pinfunction "2_2") (pintype "unspecified"))
    )
    (net (code "51") (name "Net-(CARD2-VDD)") (class "Default")
      (node (ref "C15") (pin "2") (pinfunction "2_2") (pintype "input"))
      (node (ref "C27") (pin "2") (pinfunction "2_2") (pintype "input"))
      (node (ref "CARD2") (pin "4") (pinfunction "VDD_4") (pintype "input"))
      (node (ref "R29") (pin "1") (pinfunction "1_1") (pintype "input"))
    )
    (net (code "52") (name "Net-(D1-K)") (class "Default")
      (node (ref "D1") (pin "1") (pinfunction "K_1") (pintype "unspecified"))
      (node (ref "HDMI1") (pin "18") (pinfunction "+5V_Power_18") (pintype "input"))
    )
    (net (code "53") (name "Net-(D2-A)") (class "Default")
      (node (ref "D2") (pin "2") (pinfunction "A_2") (pintype "unspecified"))
      (node (ref "USB5") (pin "1") (pinfunction "VBUS_1") (pintype "unspecified"))
    )
    (net (code "54") (name "Net-(HDMI1-TMDS_Clock+)") (class "Default")
      (node (ref "HDMI1") (pin "10") (pinfunction "TMDS_Clock+_10") (pintype "input"))
      (node (ref "R67") (pin "2") (pinfunction "2_2") (pintype "input"))
    )
    (net (code "55") (name "Net-(HDMI1-TMDS_Clock-)") (class "Default")
      (node (ref "HDMI1") (pin "12") (pinfunction "TMDS_Clock-_12") (pintype "input"))
      (node (ref "R68") (pin "2") (pinfunction "2_2") (pintype "input"))
    )
    (net (code "56") (name "Net-(HDMI1-TMDS_Data0+)") (class "Default")
      (node (ref "HDMI1") (pin "7") (pinfunction "TMDS_Data0+_7") (pintype "input"))
      (node (ref "R65") (pin "2") (pinfunction "2_2") (pintype "input"))
    )
    (net (code "57") (name "Net-(HDMI1-TMDS_Data1+)") (class "Default")
      (node (ref "HDMI1") (pin "4") (pinfunction "TMDS_Data1+_4") (pintype "input"))
      (node (ref "R63") (pin "2") (pinfunction "2_2") (pintype "input"))
    )
    (net (code "58") (name "Net-(HDMI1-TMDS_Data1-)") (class "Default")
      (node (ref "HDMI1") (pin "6") (pinfunction "TMDS_Data1-_6") (pintype "input"))
      (node (ref "R64") (pin "2") (pinfunction "2_2") (pintype "input"))
    )
    (net (code "59") (name "Net-(HDMI1-TMDS_Data2+)") (class "Default")
      (node (ref "HDMI1") (pin "1") (pinfunction "TMDS_Data2+_1") (pintype "input"))
      (node (ref "R61") (pin "2") (pinfunction "2_2") (pintype "input"))
    )
    (net (code "60") (name "Net-(HDMI1-TMDS_Data2-)") (class "Default")
      (node (ref "HDMI1") (pin "3") (pinfunction "TMDS_Data2-_3") (pintype "input"))
      (node (ref "R62") (pin "2") (pinfunction "2_2") (pintype "input"))
    )
    (net (code "61") (name "Net-(HDMI1-TMDS_Data_0-)") (class "Default")
      (node (ref "HDMI1") (pin "9") (pinfunction "TMDS_Data_0-_9") (pintype "input"))
      (node (ref "R66") (pin "2") (pinfunction "2_2") (pintype "input"))
    )
    (net (code "62") (name "Net-(L22-Pad2)") (class "Default")
      (node (ref "L22") (pin "2") (pinfunction "2_2") (pintype "input"))
      (node (ref "R34") (pin "1") (pinfunction "1_1") (pintype "input"))
    )
    (net (code "63") (name "Net-(L23-Pad2)") (class "Default")
      (node (ref "L23") (pin "2") (pinfunction "2_2") (pintype "input"))
      (node (ref "R35") (pin "1") (pinfunction "1_1") (pintype "input"))
    )
    (net (code "64") (name "Net-(LED3-A)") (class "Default")
      (node (ref "LED3") (pin "1") (pinfunction "A_1") (pintype "unspecified"))
      (node (ref "Q1") (pin "1") (pinfunction "G_1") (pintype "unspecified"))
      (node (ref "R56") (pin "1") (pinfunction "1_1") (pintype "input"))
    )
    (net (code "65") (name "Net-(LED3-K)") (class "Default")
      (node (ref "LED3") (pin "2") (pinfunction "K_2") (pintype "unspecified"))
      (node (ref "U20") (pin "24") (pinfunction "PWREN#_24") (pintype "unspecified"))
    )
    (net (code "66") (name "Net-(Q1-D)") (class "Default")
      (node (ref "F1") (pin "1") (pinfunction "1_1") (pintype "input"))
      (node (ref "Q1") (pin "3") (pinfunction "D_3") (pintype "unspecified"))
      (node (ref "R54") (pin "2") (pinfunction "2_2") (pintype "input"))
    )
    (net (code "67") (name "Net-(R33-Pad2)") (class "Default")
      (node (ref "R33") (pin "2") (pinfunction "2_2") (pintype "input"))
      (node (ref "USB2") (pin "1") (pinfunction "EP_1") (pintype "input"))
      (node (ref "USB2") (pin "2") (pinfunction "EP_2") (pintype "input"))
      (node (ref "USB2") (pin "3") (pinfunction "EP_3") (pintype "input"))
      (node (ref "USB2") (pin "4") (pinfunction "EP_4") (pintype "input"))
    )
    (net (code "68") (name "Net-(U19-VBAT)") (class "Default")
      (node (ref "BT6") (pin "1") (pinfunction "1_1") (pintype "input"))
      (node (ref "C63") (pin "1") (pinfunction "1_1") (pintype "input"))
      (node (ref "U19") (pin "6") (pinfunction "VBAT_6") (pintype "unspecified"))
    )
    (net (code "69") (name "Net-(U20-DMU)") (class "Default")
      (node (ref "CN4") (pin "2") (pinfunction "2_2") (pintype "input"))
      (node (ref "U20") (pin "14") (pinfunction "DMU_14") (pintype "unspecified"))
    )
    (net (code "70") (name "Net-(U20-DPU)") (class "Default")
      (node (ref "CN4") (pin "4") (pinfunction "4_4") (pintype "input"))
      (node (ref "U20") (pin "15") (pinfunction "DPU_15") (pintype "unspecified"))
    )
    (net (code "71") (name "Net-(U20-LED1)") (class "Default")
      (node (ref "R58") (pin "1") (pinfunction "1_1") (pintype "input"))
      (node (ref "U20") (pin "22") (pinfunction "LED1_22") (pintype "unspecified"))
    )
    (net (code "72") (name "Net-(U20-LED2)") (class "Default")
      (node (ref "R57") (pin "1") (pinfunction "1_1") (pintype "input"))
      (node (ref "U20") (pin "23") (pinfunction "LED2_23") (pintype "unspecified"))
    )
    (net (code "73") (name "Net-(U20-OVCUR#)") (class "Default")
      (node (ref "R54") (pin "1") (pinfunction "1_1") (pintype "input"))
      (node (ref "R55") (pin "2") (pinfunction "2_2") (pintype "input"))
      (node (ref "U20") (pin "1") (pinfunction "OVCUR#_1") (pintype "unspecified"))
    )
    (net (code "74") (name "Net-(U20-XI)") (class "Default")
      (node (ref "U20") (pin "4") (pinfunction "XI_4") (pintype "unspecified"))
      (node (ref "X1") (pin "1") (pinfunction "OSC1_1") (pintype "unspecified"))
    )
    (net (code "75") (name "Net-(U20-XO)") (class "Default")
      (node (ref "U20") (pin "3") (pinfunction "XO_3") (pintype "unspecified"))
      (node (ref "X1") (pin "3") (pinfunction "OSC2_3") (pintype "unspecified"))
    )
    (net (code "76") (name "Net-(U24-RESET)") (class "Default")
      (node (ref "R60") (pin "2") (pinfunction "2_2") (pintype "input"))
      (node (ref "U24") (pin "2") (pinfunction "RESET_2") (pintype "unspecified"))
    )
    (net (code "77") (name "Net-(USB2-CC1)") (class "Default")
      (node (ref "R32") (pin "2") (pinfunction "2_2") (pintype "input"))
      (node (ref "USB2") (pin "A5") (pinfunction "CC1_A5") (pintype "input"))
    )
    (net (code "78") (name "Net-(USB2-CC2)") (class "Default")
      (node (ref "R31") (pin "2") (pinfunction "2_2") (pintype "input"))
      (node (ref "USB2") (pin "B5") (pinfunction "CC2_B5") (pintype "input"))
    )
    (net (code "79") (name "Net-(USB5-D+)") (class "Default")
      (node (ref "CN4") (pin "3") (pinfunction "3_3") (pintype "input"))
      (node (ref "U1") (pin "TP3") (pinfunction "TP3_TP3") (pintype "input"))
      (node (ref "USB5") (pin "3") (pinfunction "D+_3") (pintype "unspecified"))
    )
    (net (code "80") (name "Net-(USB5-D-)") (class "Default")
      (node (ref "CN4") (pin "1") (pinfunction "1_1") (pintype "input"))
      (node (ref "U1") (pin "TP2") (pinfunction "TP2_TP2") (pintype "input"))
      (node (ref "USB5") (pin "2") (pinfunction "D-_2") (pintype "unspecified"))
    )
    (net (code "81") (name "RESET") (class "Default")
      (node (ref "R60") (pin "1") (pinfunction "1_1") (pintype "input"))
      (node (ref "SW15") (pin "2") (pinfunction "2_2") (pintype "input"))
      (node (ref "U1") (pin "30") (pinfunction "RUN_30") (pintype "input"))
      (node (ref "U20") (pin "16") (pinfunction "RESET#/CDP_16") (pintype "unspecified"))
    )
    (net (code "82") (name "SPIRX") (class "Default")
      (node (ref "CARD2") (pin "7") (pinfunction "DAT0_7") (pintype "input"))
      (node (ref "H1") (pin "3-2") (pinfunction "3-2_3-2") (pintype "unspecified"))
    )
    (net (code "83") (name "SPISCK") (class "Default")
      (node (ref "CARD2") (pin "5") (pinfunction "CLX_5") (pintype "input"))
      (node (ref "H1") (pin "1-2") (pinfunction "1-2_1-2") (pintype "unspecified"))
    )
    (net (code "84") (name "SPITX") (class "Default")
      (node (ref "CARD2") (pin "3") (pinfunction "CMD_3") (pintype "input"))
      (node (ref "H1") (pin "2-2") (pinfunction "2-2_2-2") (pintype "unspecified"))
    )
    (net (code "85") (name "VCC") (class "Default")
      (node (ref "ACTIVE") (pin "2") (pinfunction "A_2") (pintype "input"))
      (node (ref "C22") (pin "2") (pinfunction "2_2") (pintype "input"))
      (node (ref "C26") (pin "2") (pinfunction "2_2") (pintype "input"))
      (node (ref "C34") (pin "1") (pinfunction "1_1") (pintype "input"))
      (node (ref "C60") (pin "2") (pinfunction "2_2") (pintype "input"))
      (node (ref "C66") (pin "2") (pinfunction "2_2") (pintype "input"))
      (node (ref "R29") (pin "2") (pinfunction "2_2") (pintype "input"))
      (node (ref "R52") (pin "2") (pinfunction "2_2") (pintype "input"))
      (node (ref "R53") (pin "2") (pinfunction "2_2") (pintype "input"))
      (node (ref "U1") (pin "35") (pinfunction "ADC_VREF_35") (pintype "input"))
      (node (ref "U1") (pin "36") (pinfunction "3V3(OUT)_36") (pintype "input"))
      (node (ref "U19") (pin "2") (pinfunction "VCC_2") (pintype "unspecified"))
      (node (ref "U19") (pin "4") (pinfunction "RST#_4") (pintype "bidirectional"))
      (node (ref "U20") (pin "20") (pinfunction "VDD33_20") (pintype "unspecified"))
      (node (ref "U21") (pin "2") (pinfunction "VOUT_2") (pintype "input"))
      (node (ref "U21") (pin "4") (pinfunction "VOUT_4") (pintype "input"))
      (node (ref "U23") (pin "21") (pinfunction "21_21") (pintype "unspecified"))
      (node (ref "U23") (pin "22") (pinfunction "22_22") (pintype "unspecified"))
      (node (ref "U23") (pin "3") (pinfunction "3_3") (pintype "unspecified"))
      (node (ref "U23") (pin "4") (pinfunction "4_4") (pintype "unspecified"))
      (node (ref "U24") (pin "3") (pinfunction "VDD_3") (pintype "unspecified"))
      (node (ref "U7") (pin "16") (pinfunction "VCC_16") (pintype "input"))
      (node (ref "U7") (pin "4") (pinfunction "V3_4") (pintype "input"))
    )
    (net (code "86") (name "unconnected-(CARD2-DAT1-Pad8)") (class "Default")
      (node (ref "CARD2") (pin "8") (pinfunction "DAT1_8") (pintype "input+no_connect"))
    )
    (net (code "87") (name "unconnected-(CARD2-DAT2-Pad1)") (class "Default")
      (node (ref "CARD2") (pin "1") (pinfunction "DAT2_1") (pintype "input+no_connect"))
    )
    (net (code "88") (name "unconnected-(CARD2-PadCD)") (class "Default")
      (node (ref "CARD2") (pin "CD") (pinfunction "CD_CD") (pintype "input+no_connect"))
    )
    (net (code "89") (name "unconnected-(HDMI1-CEC-Pad13)") (class "Default")
      (node (ref "HDMI1") (pin "13") (pinfunction "CEC_13") (pintype "input+no_connect"))
    )
    (net (code "90") (name "unconnected-(HDMI1-Hot_Plug_Detect-Pad19)") (class "Default")
      (node (ref "HDMI1") (pin "19") (pinfunction "Hot_Plug_Detect_19") (pintype "input+no_connect"))
    )
    (net (code "91") (name "unconnected-(HDMI1-Reserved(N.C.)-Pad14)") (class "Default")
      (node (ref "HDMI1") (pin "14") (pinfunction "Reserved(N.C.)_14") (pintype "input+no_connect"))
    )
    (net (code "92") (name "unconnected-(HDMI1-SCL-Pad15)") (class "Default")
      (node (ref "HDMI1") (pin "15") (pinfunction "SCL_15") (pintype "input+no_connect"))
    )
    (net (code "93") (name "unconnected-(HDMI1-SDA-Pad16)") (class "Default")
      (node (ref "HDMI1") (pin "16") (pinfunction "SDA_16") (pintype "input+no_connect"))
    )
    (net (code "94") (name "unconnected-(U1-GND-Pad42)") (class "Default")
      (node (ref "U1") (pin "42") (pinfunction "GND_42") (pintype "input+no_connect"))
    )
    (net (code "95") (name "unconnected-(U1-PadTP1)") (class "Default")
      (node (ref "U1") (pin "TP1") (pinfunction "TP1_TP1") (pintype "input+no_connect"))
    )
    (net (code "96") (name "unconnected-(U1-PadTP5)") (class "Default")
      (node (ref "U1") (pin "TP5") (pinfunction "TP5_TP5") (pintype "input+no_connect"))
    )
    (net (code "97") (name "unconnected-(U1-PadTP6)") (class "Default")
      (node (ref "U1") (pin "TP6") (pinfunction "TP6_TP6") (pintype "input+no_connect"))
    )
    (net (code "98") (name "unconnected-(U1-SWCLK-Pad41)") (class "Default")
      (node (ref "U1") (pin "41") (pinfunction "SWCLK_41") (pintype "input+no_connect"))
    )
    (net (code "99") (name "unconnected-(U1-SWDIO-Pad43)") (class "Default")
      (node (ref "U1") (pin "43") (pinfunction "SWDIO_43") (pintype "input+no_connect"))
    )
    (net (code "100") (name "unconnected-(U1-VBUS-Pad40)") (class "Default")
      (node (ref "U1") (pin "40") (pinfunction "VBUS_40") (pintype "input+no_connect"))
    )
    (net (code "101") (name "unconnected-(U1-VSYS-Pad39)") (class "Default")
      (node (ref "U1") (pin "39") (pinfunction "VSYS_39") (pintype "input+no_connect"))
    )
    (net (code "102") (name "unconnected-(U7-CTS#-Pad9)") (class "Default")
      (node (ref "U7") (pin "9") (pinfunction "CTS#_9") (pintype "input+no_connect"))
    )
    (net (code "103") (name "unconnected-(U7-DCD#-Pad12)") (class "Default")
      (node (ref "U7") (pin "12") (pinfunction "DCD#_12") (pintype "input+no_connect"))
    )
    (net (code "104") (name "unconnected-(U7-DSR#-Pad10)") (class "Default")
      (node (ref "U7") (pin "10") (pinfunction "DSR#_10") (pintype "input+no_connect"))
    )
    (net (code "105") (name "unconnected-(U7-DTR#-Pad13)") (class "Default")
      (node (ref "U7") (pin "13") (pinfunction "DTR#_13") (pintype "input+no_connect"))
    )
    (net (code "106") (name "unconnected-(U7-NC.-Pad7)") (class "Default")
      (node (ref "U7") (pin "7") (pinfunction "NC._7") (pintype "input+no_connect"))
    )
    (net (code "107") (name "unconnected-(U7-OUT#-Pad8)") (class "Default")
      (node (ref "U7") (pin "8") (pinfunction "OUT#_8") (pintype "input+no_connect"))
    )
    (net (code "108") (name "unconnected-(U7-R232-Pad15)") (class "Default")
      (node (ref "U7") (pin "15") (pinfunction "R232_15") (pintype "input+no_connect"))
    )
    (net (code "109") (name "unconnected-(U7-RI#-Pad11)") (class "Default")
      (node (ref "U7") (pin "11") (pinfunction "RI#_11") (pintype "input+no_connect"))
    )
    (net (code "110") (name "unconnected-(U7-RTS#-Pad14)") (class "Default")
      (node (ref "U7") (pin "14") (pinfunction "RTS#_14") (pintype "input+no_connect"))
    )
    (net (code "111") (name "unconnected-(U19-32kHz-Pad1)") (class "Default")
      (node (ref "U19") (pin "1") (pinfunction "32kHz_1") (pintype "unspecified+no_connect"))
    )
    (net (code "112") (name "unconnected-(U19-INT#{slash}SQW-Pad3)") (class "Default")
      (node (ref "U19") (pin "3") (pinfunction "INT#/SQW_3") (pintype "bidirectional+no_connect"))
    )
    (net (code "113") (name "unconnected-(U20-LED3{slash}SCL-Pad13)") (class "Default")
      (node (ref "U20") (pin "13") (pinfunction "LED3/SCL_13") (pintype "unspecified+no_connect"))
    )
    (net (code "114") (name "unconnected-(U20-NC-Pad17)") (class "Default")
      (node (ref "U20") (pin "17") (pinfunction "NC_17") (pintype "unspecified+no_connect"))
    )
    (net (code "115") (name "unconnected-(U20-NC.-Pad2)") (class "Default")
      (node (ref "U20") (pin "2") (pinfunction "NC._2") (pintype "unspecified+no_connect"))
    )
    (net (code "116") (name "unconnected-(U20-PSELF-Pad18)") (class "Default")
      (node (ref "U20") (pin "18") (pinfunction "PSELF_18") (pintype "unspecified+no_connect"))
    )
    (net (code "117") (name "unconnected-(USB2-SUB1-PadA8)") (class "Default")
      (node (ref "USB2") (pin "A8") (pinfunction "SUB1_A8") (pintype "input+no_connect"))
    )
    (net (code "118") (name "unconnected-(USB2-SUB2-PadB8)") (class "Default")
      (node (ref "USB2") (pin "B8") (pinfunction "SUB2_B8") (pintype "input+no_connect"))
    )
    (net (code "119") (name "unconnected-(USB5-ID-Pad4)") (class "Default")
      (node (ref "USB5") (pin "4") (pinfunction "ID_4") (pintype "unspecified+no_connect"))
    )
  )
)
